# Minimum_system.net
KiCad netlist of a schematic drawn in Altium Designer
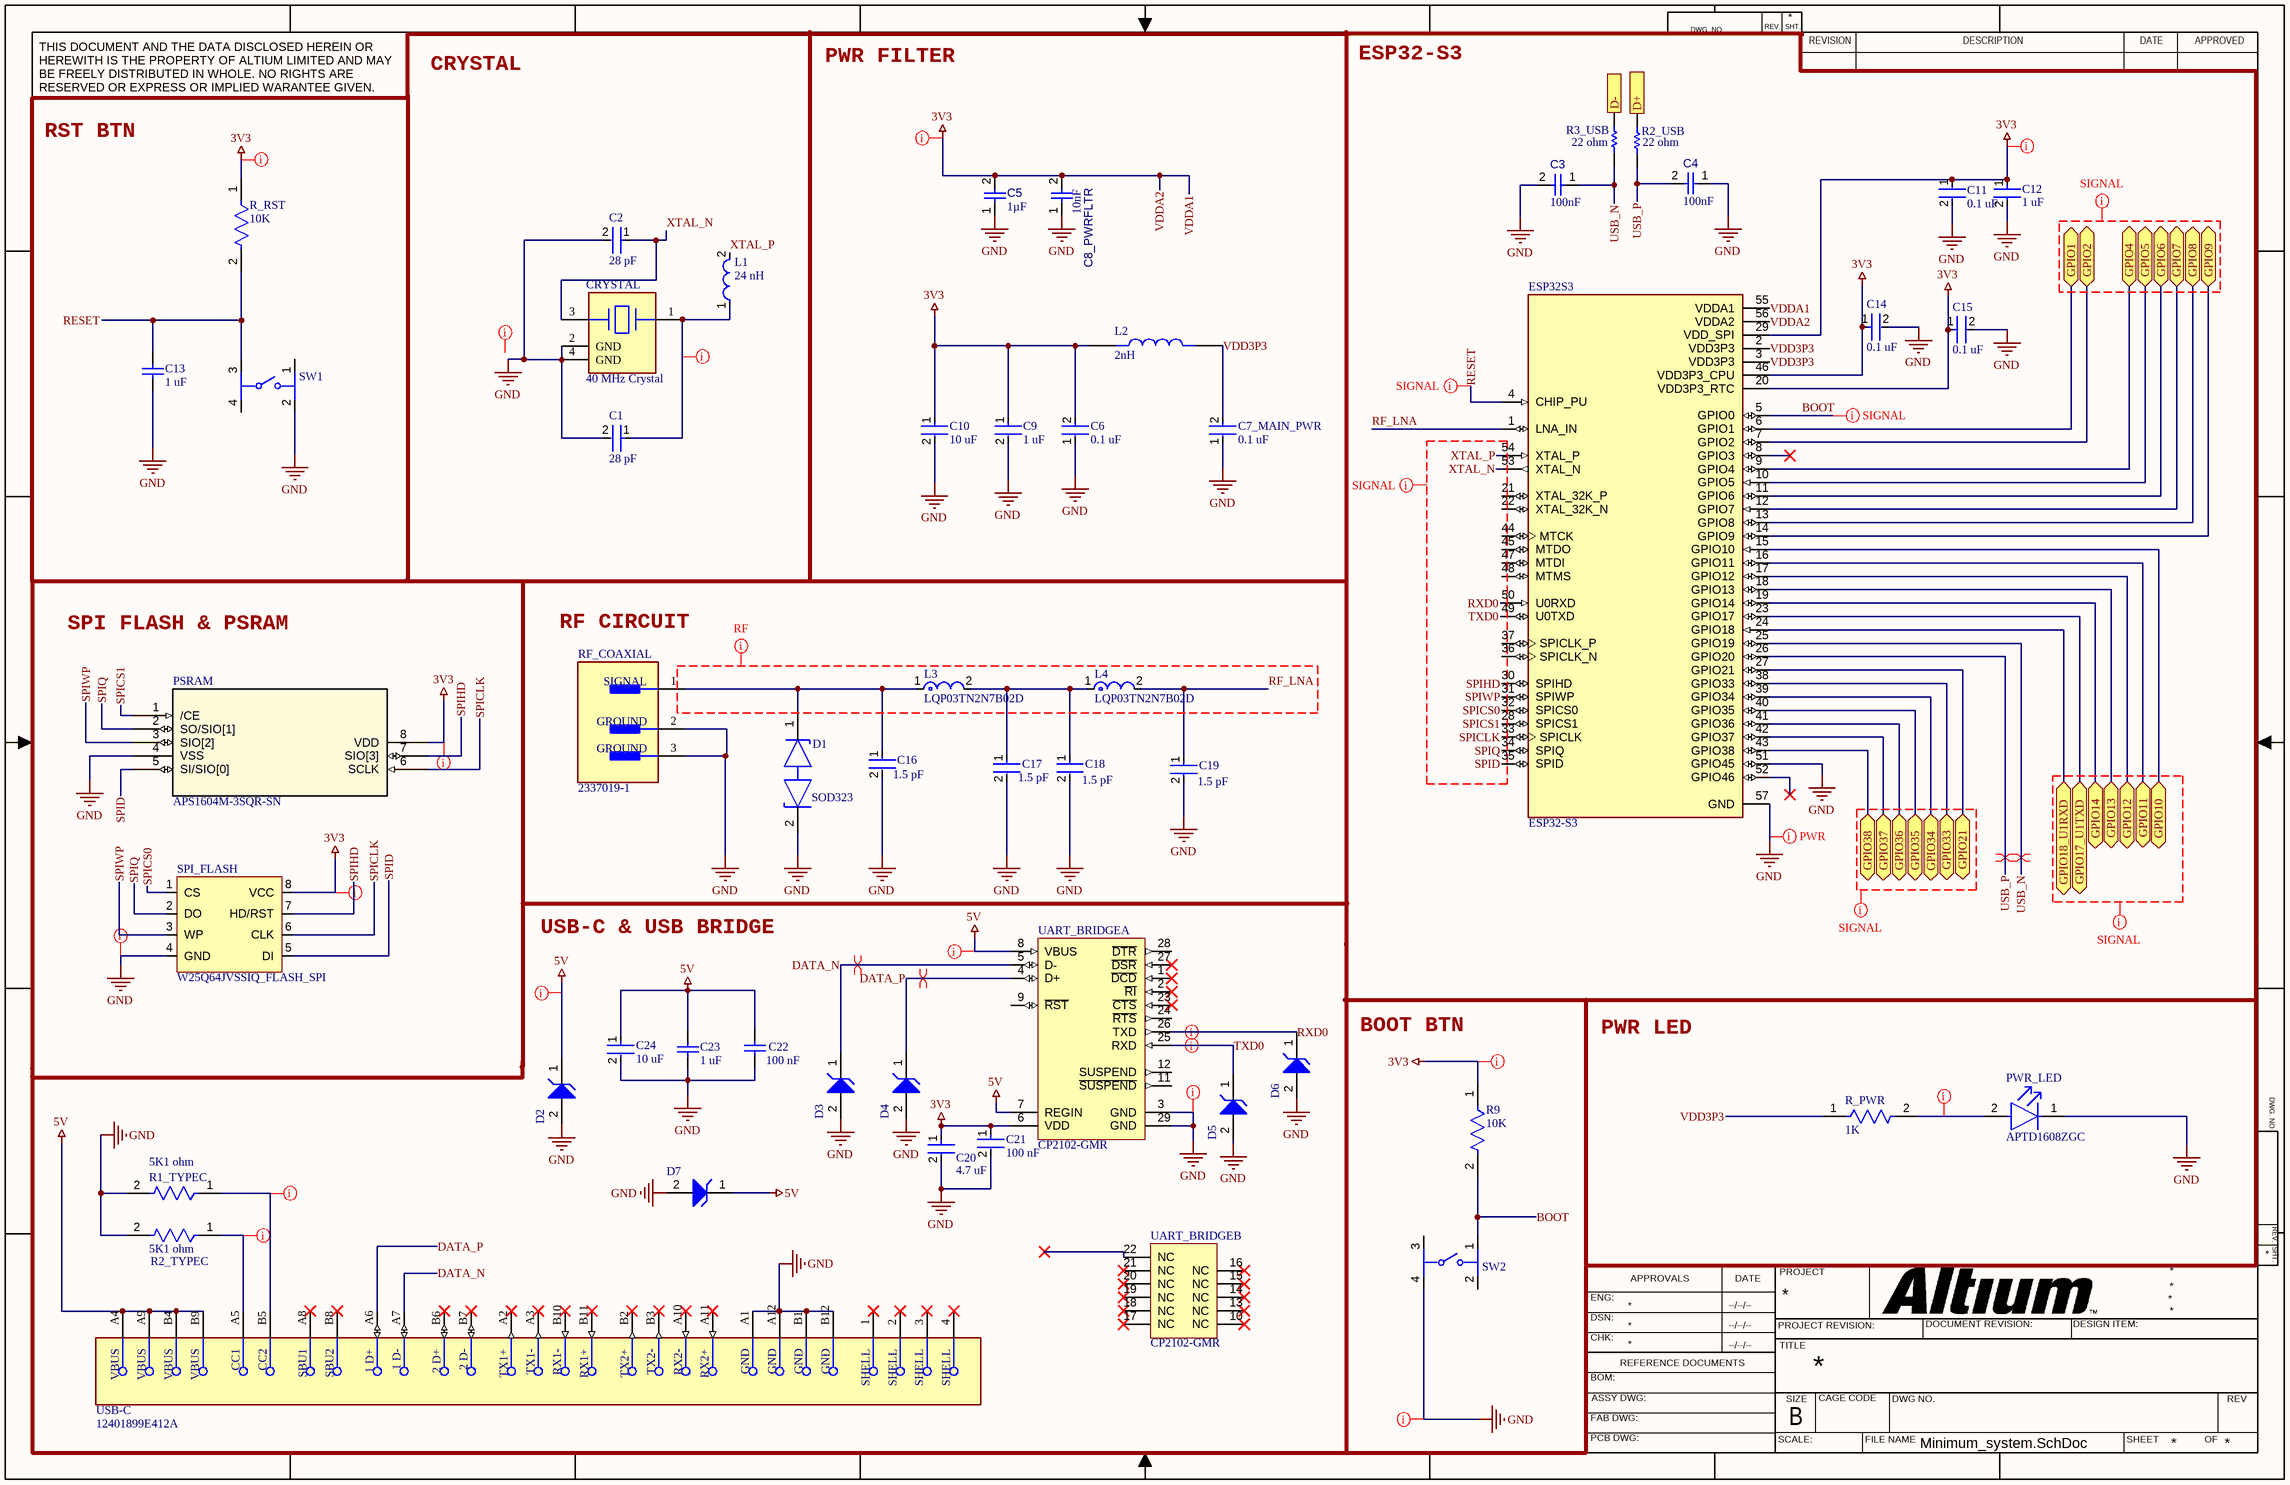
[diagram p0: Minimum_system.SchDoc]

(export (version "E")
  (design (tool "Eeschema 10.0.6"))
  (components
    (comp (ref "C1")
      (value "28 pF")
      (footprint "FP-GQM219-0_15-MFG")
      (description "Ceramic Capacitor 28pF ±2% 250VDC C0G 0805 Paper T/R")
      (libsource (lib "Altium Content Vault") (part "b4654b650e69147ec39a6b967a45e02"))
    )
    (comp (ref "C2")
      (value "28 pF")
      (footprint "FP-GQM219-0_15-MFG")
      (description "Ceramic Capacitor 28pF ±2% 250VDC C0G 0805 Paper T/R")
      (libsource (lib "Altium Content Vault") (part "b4654b650e69147ec39a6b967a45e02"))
    )
    (comp (ref "C3")
      (value "100nF")
      (footprint "CAPC0402(1005)60_L")
      (description "Chip Capacitor, 100nF +/-20%, 50V, 0402, Thickness 0.6 mm")
      (fields (field (name "TOLERANCE") "10%") (field (name "Comment") "Capacitor 100nF +/-20% 50V 0402"))
      (libsource (lib "Faiz Agunda") (part "CAP-NP-2"))
    )
    (comp (ref "C4")
      (value "100nF")
      (footprint "CAPC0402(1005)60_L")
      (description "Chip Capacitor, 100nF +/-20%, 50V, 0402, Thickness 0.6 mm")
      (fields (field (name "TOLERANCE") "10%") (field (name "Comment") "Capacitor 100nF +/-20% 50V 0402"))
      (libsource (lib "Faiz Agunda") (part "CAP-NP-2"))
    )
    (comp (ref "C5")
      (value "1µF")
      (footprint "CAPC1608X90X35ML15T15")
      (description "Chip Capacitor, 1 uF, +/- 10%, 16 V, 0603 (1608 Metric)")
      (fields (field (name "TOLERANCE") "10%") (field (name "Comment") "Capacitor 1uF +/- 10% 16V 0603"))
      (libsource (lib "Faiz Agunda") (part "CAP-NP-2"))
    )
    (comp (ref "C6")
      (value "0.1 uF")
      (footprint "FP-C1608-080-0_1-IPC_B")
      (description "Multilayer Ceramic Capacitors 100nF ±10% 50V X7R SMD 0603")
      (fields (field (name "VOLTAGE") "50V") (field (name "TOLERANCE") "10%"))
      (libsource (lib "Altium Content Vault") (part "236180d848d6139a670b325ea6854c9"))
    )
    (comp (ref "C7_MAIN_PWR")
      (value "0.1 uF")
      (footprint "FP-C1608-080-0_1-IPC_B")
      (description "Multilayer Ceramic Capacitors 100nF ±10% 50V X7R SMD 0603")
      (fields (field (name "VOLTAGE") "50V") (field (name "TOLERANCE") "10%"))
      (libsource (lib "Altium Content Vault") (part "236180d848d6139a670b325ea6854c9"))
    )
    (comp (ref "C8_PWRFLTR")
      (value "10nF")
      (footprint "CAPC0402(1005)60_L")
      (description "Chip Capacitor, 10nF +/-20%, 50V, 0402, Thickness 0.6 mm")
      (fields (field (name "TOLERANCE") "5%") (field (name "Comment") "Capacitor 10nF +/-20% 50V 0402"))
      (libsource (lib "Faiz Agunda") (part "CAP-NP-2"))
    )
    (comp (ref "C9")
      (value "1 uF")
      (footprint "FP-GRM21B-0_2-e0_2_0_7-MFG")
      (description "Chip Multilayer Ceramic Capacitors for General Purpose, 0805, 1.0uF, X7S, 22%, 10%, 100V")
      (fields (field (name "TOLERANCE") "10%"))
      (libsource (lib "Altium Content Vault") (part "b4654b650e69147ec39a6b967a45e02"))
    )
    (comp (ref "C10")
      (value "10 uF")
      (footprint "FP-GRM188-0_15-IPC_C")
      (description "Chip Multilayer Ceramic Capacitors for General Purpose, 0603, 10uF, X5R, 15%, 20%, 10V")
      (fields (field (name "TOLERANCE") "20%"))
      (libsource (lib "Altium Content Vault") (part "02cd4be3c70576c341d710602a673aa"))
    )
    (comp (ref "C11")
      (value "0.1 uF")
      (footprint "FP-C1608-080-0_1-IPC_B")
      (description "Multilayer Ceramic Capacitors 100nF ±10% 50V X7R SMD 0603")
      (fields (field (name "VOLTAGE") "50V") (field (name "TOLERANCE") "10%"))
      (libsource (lib "Altium Content Vault") (part "236180d848d6139a670b325ea6854c9"))
    )
    (comp (ref "C12")
      (value "1 uF")
      (footprint "FP-GRM21B-0_2-e0_2_0_7-MFG")
      (description "Chip Multilayer Ceramic Capacitors for General Purpose, 0805, 1.0uF, X7S, 22%, 10%, 100V")
      (fields (field (name "TOLERANCE") "10%"))
      (libsource (lib "Altium Content Vault") (part "b4654b650e69147ec39a6b967a45e02"))
    )
    (comp (ref "C13")
      (value "1 uF")
      (footprint "CAPC2013X140X50NL20T25")
      (fields
        (field (name "PART NUMBER") "0805YD105MAT2A")
        (field (name "MANUFACTURER") "AVX Interconnect / Elco")
      )
      (libsource (lib "Altium Content Vault") (part "CAP"))
    )
    (comp (ref "C14")
      (value "0.1 uF")
      (footprint "FP-CC0201-BA-MFG")
      (description "CC0201 100 nF X5R 20.00% 10 V")
      (fields (field (name "TOLERANCE") "0.2") (field (name "MANUFACTURER") "Yageo"))
      (libsource (lib "Altium Content Vault") (part "11868f565c42a9108669ba33697ecf6"))
    )
    (comp (ref "C15")
      (value "0.1 uF")
      (footprint "FP-CC0201-BA-MFG")
      (description "CC0201 100 nF X5R 20.00% 10 V")
      (fields (field (name "TOLERANCE") "0.2") (field (name "MANUFACTURER") "Yageo"))
      (libsource (lib "Altium Content Vault") (part "11868f565c42a9108669ba33697ecf6"))
    )
    (comp (ref "C16")
      (value "1.5 pF")
      (footprint "FP-GRM033-0_03-MFG")
      (description "Chip Multilayer Ceramic Capacitors for General Purpose, 0201, 1.5pF, C0G, 30ppm/°C, 0.1pF, 50V")
      (libsource (lib "Altium Content Vault") (part "b4654b650e69147ec39a6b967a45e02"))
    )
    (comp (ref "C17")
      (value "1.5 pF")
      (footprint "FP-GRM033-0_03-MFG")
      (description "Chip Multilayer Ceramic Capacitors for General Purpose, 0201, 1.5pF, C0G, 30ppm/°C, 0.1pF, 50V")
      (libsource (lib "Altium Content Vault") (part "b4654b650e69147ec39a6b967a45e02"))
    )
    (comp (ref "C18")
      (value "1.5 pF")
      (footprint "FP-GRM033-0_03-MFG")
      (description "Chip Multilayer Ceramic Capacitors for General Purpose, 0201, 1.5pF, C0G, 30ppm/°C, 0.1pF, 50V")
      (libsource (lib "Altium Content Vault") (part "b4654b650e69147ec39a6b967a45e02"))
    )
    (comp (ref "C19")
      (value "1.5 pF")
      (footprint "FP-GRM033-0_03-MFG")
      (description "Chip Multilayer Ceramic Capacitors for General Purpose, 0201, 1.5pF, C0G, 30ppm/°C, 0.1pF, 50V")
      (libsource (lib "Altium Content Vault") (part "b4654b650e69147ec39a6b967a45e02"))
    )
    (comp (ref "C20")
      (value "4.7 uF")
      (footprint "FP-GCJ31C-0_3-IPC_C")
      (description "Cap Ceramic 4.7uF 16V X7R 10% Pad SMD 1206 Soft Termination  +125°C Automotive T/R")
      (libsource (lib "Altium Content Vault") (part "b4654b650e69147ec39a6b967a45e02"))
    )
    (comp (ref "C21")
      (value "100 nF")
      (footprint "FP-GRM155-0_05-MFG")
      (description "Chip Multilayer Ceramic Capacitors for General Purpose, 0402, 0.10uF, X7R, 15%, 20%, 50V")
      (libsource (lib "Altium Content Vault") (part "02cd4be3c70576c341d710602a673aa"))
    )
    (comp (ref "C22")
      (value "100 nF")
      (footprint "CAPC0603X33X15NL03T05")
      (fields
        (field (name "PART NUMBER") "02016D104KAT4A")
        (field (name "MANUFACTURER") "AVX Interconnect / Elco")
      )
      (libsource (lib "Altium Content Vault") (part "CAP"))
    )
    (comp (ref "C23")
      (value "1 uF")
      (footprint "CAPC2013X140X50NL20T25")
      (fields
        (field (name "PART NUMBER") "0805YD105MAT2A")
        (field (name "MANUFACTURER") "AVX Interconnect / Elco")
      )
      (libsource (lib "Altium Content Vault") (part "CAP"))
    )
    (comp (ref "C24")
      (value "10 uF")
      (footprint "FP-GRM188-0_15-IPC_C")
      (description "Chip Multilayer Ceramic Capacitors for General Purpose, 0603, 10uF, X5R, 15%, 20%, 10V")
      (fields (field (name "TOLERANCE") "20%"))
      (libsource (lib "Altium Content Vault") (part "02cd4be3c70576c341d710602a673aa"))
    )
    (comp (ref "CRYSTAL")
      (value "40 MHz Crystal")
      (footprint "FP-ABM8AIG-MFG")
      (description "Crystal 40MHz ±20ppm (Tol) ±100ppm (Stability) 12pF FUND 35Ω Automotive 4-Pin Ultra Mini-CSMD T/R")
      (libsource (lib "Altium Content Vault") (part "5645ab55de99a04feaa93ac4102b7fe"))
    )
    (comp (ref "D1")
      (value "SOD323")
      (footprint "FP-SOD323-CA-MFG")
      (description "TVS DIODE 5V 14V SOD323")
      (libsource (lib "Altium Content Vault") (part "f6dbb2535d6b2d347ec798cb4d032a4"))
    )
    (comp (ref "D2")
      (value "824520581")
      (footprint "WE-TVSP_DO-214AA_Unidirectional")
      (description "TVS diode [Würth Elektronik] 824520581 TVS diode")
      (libsource (lib "Altium Content Vault") (part "WE-TVSP_Unidirectional"))
    )
    (comp (ref "D3")
      (value "824520581")
      (footprint "WE-TVSP_DO-214AA_Unidirectional")
      (description "TVS diode [Würth Elektronik] 824520581 TVS diode")
      (libsource (lib "Altium Content Vault") (part "WE-TVSP_Unidirectional"))
    )
    (comp (ref "D4")
      (value "824520581")
      (footprint "WE-TVSP_DO-214AA_Unidirectional")
      (description "TVS diode [Würth Elektronik] 824520581 TVS diode")
      (libsource (lib "Altium Content Vault") (part "WE-TVSP_Unidirectional"))
    )
    (comp (ref "D5")
      (value "824520581")
      (footprint "WE-TVSP_DO-214AA_Unidirectional")
      (description "TVS diode [Würth Elektronik] 824520581 TVS diode")
      (libsource (lib "Altium Content Vault") (part "WE-TVSP_Unidirectional"))
    )
    (comp (ref "D6")
      (value "824520581")
      (footprint "WE-TVSP_DO-214AA_Unidirectional")
      (description "TVS diode [Würth Elektronik] 824520581 TVS diode")
      (libsource (lib "Altium Content Vault") (part "WE-TVSP_Unidirectional"))
    )
    (comp (ref "D7")
      (value "824520581")
      (footprint "WE-TVSP_DO-214AA_Unidirectional")
      (description "TVS diode [Würth Elektronik] 824520581 TVS diode")
      (libsource (lib "Altium Content Vault") (part "WE-TVSP_Unidirectional"))
    )
    (comp (ref "ESP32S3")
      (value "ESP32-S3")
      (footprint "IC_ESP32-S3")
      (fields (field (name "MF") "Espressif Systems"))
      (libsource (lib "Faiz Agunda") (part "ESP32-S3"))
    )
    (comp (ref "L1")
      (value "24 nH")
      (footprint "FP-LQW15AN_00-W0_5-0_1-MFG")
      (description "Wire Wound RF Inductor 24nH ±2% 280mA 0.52Ω 0402 (1005)")
      (fields (field (name "TOLERANCE") "2%"))
      (libsource (lib "Altium Content Vault") (part "725321dda6339637d4d059423bc1c3c"))
    )
    (comp (ref "L2")
      (value "2nH")
      (footprint "INDC0603X28N")
      (fields (field (name "MP") "ATFC-0201HQ-2N0B-T") (field (name "MF") "{'manufacturer': u'Abracon LLC'}"))
      (libsource (lib "Faiz Agunda") (part "ATFC-0201HQ-2N0B-T"))
    )
    (comp (ref "L3")
      (value "LQP03TN2N7B02D")
      (footprint "FP-LQP03TG_02-IPC_A")
      (description "Film type RF Inductor 2.7nH ±0.1nH 500mA 0.2Ω 0201 (0603)")
      (fields (field (name "TOLERANCE") "3%"))
      (libsource (lib "Altium Content Vault") (part "4cc4b267dca4c8e51f7102f422741d8"))
    )
    (comp (ref "L4")
      (value "LQP03TN2N7B02D")
      (footprint "FP-LQP03TG_02-IPC_A")
      (description "Film type RF Inductor 2.7nH ±0.1nH 500mA 0.2Ω 0201 (0603)")
      (fields (field (name "TOLERANCE") "3%"))
      (libsource (lib "Altium Content Vault") (part "4cc4b267dca4c8e51f7102f422741d8"))
    )
    (comp (ref "PSRAM")
      (value "APS1604M-3SQR-SN")
      (footprint "SOP8L_APS1604M-3SQR-SN_APY")
      (description "2 MB PSRAM SPI")
      (fields (field (name "COPYRIGHT") "Copyright (C) 2026 Ultra Librarian. All rights reserved."))
      (libsource (lib "Faiz Agunda") (part "APS1604M-3SQR-SN"))
    )
    (comp (ref "PWR_LED")
      (value "APTD1608ZGC")
      (footprint "FP-APTD1608ZGC-MFG")
      (description "LED GREEN CLEAR CHIP SMD")
      (libsource (lib "Altium Content Vault") (part "8706943c75ba83719d021d2fdc84c58"))
    )
    (comp (ref "R1_TYPEC")
      (value "5K1 ohm")
      (footprint "FP-CRCW1206-e3-IPC_B")
      (description "RES Thick Film, 5.1kΩ, 5%, 0.25W, 200ppm/°C, 1206")
      (fields (field (name "TOLERANCE") "5%"))
      (libsource (lib "Altium Content Vault") (part "1029c3af85768c4190bb7ad29bc67b5"))
    )
    (comp (ref "R2_TYPEC")
      (value "5K1 ohm")
      (footprint "FP-CRCW1206-e3-IPC_B")
      (description "RES Thick Film, 5.1kΩ, 5%, 0.25W, 200ppm/°C, 1206")
      (fields (field (name "TOLERANCE") "5%"))
      (libsource (lib "Altium Content Vault") (part "1029c3af85768c4190bb7ad29bc67b5"))
    )
    (comp (ref "R2_USB")
      (value "22 ohm")
      (footprint "RESC1608X55X25LL10T15")
      (fields (field (name "MANUFACTURER") "Yageo") (field (name "PART NUMBER") "RC0603FR-1022RL"))
      (libsource (lib "Altium Content Vault") (part "RES"))
    )
    (comp (ref "R3_USB")
      (value "22 ohm")
      (footprint "RESC1608X55X25LL10T15")
      (fields (field (name "MANUFACTURER") "Yageo") (field (name "PART NUMBER") "RC0603FR-1022RL"))
      (libsource (lib "Altium Content Vault") (part "RES"))
    )
    (comp (ref "R9")
      (value "10K")
      (footprint "FP-AC0603-IPC_A")
      (description "RES 10kΩ 5.00% 0.2W 0603")
      (libsource (lib "Altium Content Vault") (part "1029c3af85768c4190bb7ad29bc67b5"))
    )
    (comp (ref "RF_COAXIAL")
      (value "2337019-1")
      (footprint "FP-2337019-1-MFG")
      (description "UMCC MICRO-COAX RECEPTACLE, GEN")
      (libsource (lib "Altium Content Vault") (part "3efd87c86022015edd7e825a7948772"))
    )
    (comp (ref "R_PWR")
      (value "1K")
      (footprint "FP-RP732B-MFG")
      (description "Res Thin Film 1206 1.0KΩ 0.1% 0.25W 15ppm/°C Molded SMD")
      (fields
        (field (name "TOLERANCE") "0.1%")
        (field (name "OCTOPART") "https://octopart.com/rp73d2b1k0btdf-te+connectivity-22741139")
      )
      (libsource (lib "Altium Content Vault") (part "1029c3af85768c4190bb7ad29bc67b5"))
    )
    (comp (ref "R_RST")
      (value "10K")
      (footprint "FP-AC0603-IPC_A")
      (description "RES 10kΩ 5.00% 0.2W 0603")
      (libsource (lib "Altium Content Vault") (part "1029c3af85768c4190bb7ad29bc67b5"))
    )
    (comp (ref "SPI_FLASH")
      (value "W25Q64JVSSIQ_FLASH_SPI")
      (footprint "SOIC127P790X216-8N")
      (description "8 MB flash SPI")
      (libsource (lib "Faiz Agunda") (part "Component_1"))
    )
    (comp (ref "SW1")
      (value "PTS810SJM250SMTRLFS")
      (footprint "FP-PTS810SJM250SMTRLFS-MFG")
      (description "SWITCH TACTILE SPST-NO 0.05A 16V")
      (libsource (lib "Altium Content Vault") (part "1adf0dd01260c80cf25a44bfd6b99ba"))
    )
    (comp (ref "SW2")
      (value "PTS810SJM250SMTRLFS")
      (footprint "FP-PTS810SJM250SMTRLFS-MFG")
      (description "SWITCH TACTILE SPST-NO 0.05A 16V")
      (libsource (lib "Altium Content Vault") (part "1adf0dd01260c80cf25a44bfd6b99ba"))
    )
    (comp (ref "UART_BRIDGE")
      (value "CP2102-GMR")
      (footprint "SLAB-QFN-28-3125x3125TP_M")
      (description "Single-Chip USB to URAT Bridge, 3.3 V, -40 to 85 degC, 28-Pin QFN, RoHS, Tape and Reel")
      (fields (field (name "MANUFACTURER") "Silicon Labs"))
      (libsource (lib "Altium Content Vault") (part "SLAB-CP210X-QFN-28-29"))
    )
    (comp (ref "USB-C")
      (value "12401899E412A")
      (footprint "FP-12401899E412A-MFG")
      (description "USB TYPE C, RECEPTACLE, TOP MOUN")
      (libsource (lib "Altium Content Vault") (part "d6c81757777e40fb740c912bc321649"))
    )
  )
  (nets
    (net (code "2") (name "/BOOT") (class "Default")
      (node (ref "ESP32S3") (pin "5") (pinfunction "GPIO0_5") (pintype "bidirectional"))
      (node (ref "R9") (pin "2") (pinfunction "2_2") (pintype "passive"))
      (node (ref "SW2") (pin "1") (pinfunction "1_1") (pintype "passive"))
    )
    (net (code "3") (name "/D+") (class "Default")
      (node (ref "R2_USB") (pin "1") (pinfunction "1_1") (pintype "passive"))
    )
    (net (code "4") (name "/D-") (class "Default")
      (node (ref "R3_USB") (pin "1") (pinfunction "1_1") (pintype "passive"))
    )
    (net (code "5") (name "/DATA_N") (class "Default")
      (node (ref "D3") (pin "1") (pinfunction "K_1") (pintype "passive"))
      (node (ref "UART_BRIDGE") (pin "5") (pinfunction "D-_5") (pintype "bidirectional"))
      (node (ref "USB-C") (pin "A7") (pinfunction "1_D-_A7") (pintype "bidirectional"))
    )
    (net (code "6") (name "/DATA_P") (class "Default")
      (node (ref "D4") (pin "1") (pinfunction "K_1") (pintype "passive"))
      (node (ref "UART_BRIDGE") (pin "4") (pinfunction "D+_4") (pintype "bidirectional"))
      (node (ref "USB-C") (pin "A6") (pinfunction "1_D+_A6") (pintype "bidirectional"))
    )
    (net (code "7") (name "/GPIO1") (class "Default")
      (node (ref "ESP32S3") (pin "6") (pinfunction "GPIO1_6") (pintype "bidirectional"))
    )
    (net (code "8") (name "/GPIO2") (class "Default")
      (node (ref "ESP32S3") (pin "7") (pinfunction "GPIO2_7") (pintype "bidirectional"))
    )
    (net (code "9") (name "/GPIO4") (class "Default")
      (node (ref "ESP32S3") (pin "9") (pinfunction "GPIO4_9") (pintype "bidirectional"))
    )
    (net (code "10") (name "/GPIO5") (class "Default")
      (node (ref "ESP32S3") (pin "10") (pinfunction "GPIO5_10") (pintype "input"))
    )
    (net (code "11") (name "/GPIO6") (class "Default")
      (node (ref "ESP32S3") (pin "11") (pinfunction "GPIO6_11") (pintype "bidirectional"))
    )
    (net (code "12") (name "/GPIO7") (class "Default")
      (node (ref "ESP32S3") (pin "12") (pinfunction "GPIO7_12") (pintype "input"))
    )
    (net (code "13") (name "/GPIO8") (class "Default")
      (node (ref "ESP32S3") (pin "13") (pinfunction "GPIO8_13") (pintype "bidirectional"))
    )
    (net (code "14") (name "/GPIO9") (class "Default")
      (node (ref "ESP32S3") (pin "14") (pinfunction "GPIO9_14") (pintype "bidirectional"))
    )
    (net (code "15") (name "/GPIO10") (class "Default")
      (node (ref "ESP32S3") (pin "15") (pinfunction "GPIO10_15") (pintype "input"))
    )
    (net (code "16") (name "/GPIO11") (class "Default")
      (node (ref "ESP32S3") (pin "16") (pinfunction "GPIO11_16") (pintype "bidirectional"))
    )
    (net (code "17") (name "/GPIO12") (class "Default")
      (node (ref "ESP32S3") (pin "17") (pinfunction "GPIO12_17") (pintype "bidirectional"))
    )
    (net (code "18") (name "/GPIO13") (class "Default")
      (node (ref "ESP32S3") (pin "18") (pinfunction "GPIO13_18") (pintype "bidirectional"))
    )
    (net (code "19") (name "/GPIO14") (class "Default")
      (node (ref "ESP32S3") (pin "19") (pinfunction "GPIO14_19") (pintype "bidirectional"))
    )
    (net (code "20") (name "/GPIO17_U1TXD") (class "Default")
      (node (ref "ESP32S3") (pin "23") (pinfunction "GPIO17_23") (pintype "bidirectional"))
    )
    (net (code "21") (name "/GPIO18_U1RXD") (class "Default")
      (node (ref "ESP32S3") (pin "24") (pinfunction "GPIO18_24") (pintype "input"))
    )
    (net (code "22") (name "/GPIO21") (class "Default")
      (node (ref "ESP32S3") (pin "27") (pinfunction "GPIO21_27") (pintype "bidirectional"))
    )
    (net (code "23") (name "/GPIO33") (class "Default")
      (node (ref "ESP32S3") (pin "38") (pinfunction "GPIO33_38") (pintype "bidirectional"))
    )
    (net (code "24") (name "/GPIO34") (class "Default")
      (node (ref "ESP32S3") (pin "39") (pinfunction "GPIO34_39") (pintype "bidirectional"))
    )
    (net (code "25") (name "/GPIO35") (class "Default")
      (node (ref "ESP32S3") (pin "40") (pinfunction "GPIO35_40") (pintype "bidirectional"))
    )
    (net (code "26") (name "/GPIO36") (class "Default")
      (node (ref "ESP32S3") (pin "41") (pinfunction "GPIO36_41") (pintype "bidirectional"))
    )
    (net (code "27") (name "/GPIO37") (class "Default")
      (node (ref "ESP32S3") (pin "42") (pinfunction "GPIO37_42") (pintype "bidirectional"))
    )
    (net (code "28") (name "/GPIO38") (class "Default")
      (node (ref "ESP32S3") (pin "43") (pinfunction "GPIO38_43") (pintype "bidirectional"))
    )
    (net (code "29") (name "/RESET") (class "Default")
      (node (ref "C13") (pin "1") (pinfunction "1_1") (pintype "passive"))
      (node (ref "ESP32S3") (pin "4") (pinfunction "CHIP_PU_4") (pintype "input"))
      (node (ref "R_RST") (pin "2") (pinfunction "2_2") (pintype "passive"))
      (node (ref "SW1") (pin "3") (pinfunction "3_3") (pintype "passive"))
    )
    (net (code "30") (name "/RF_LNA") (class "Default")
      (node (ref "C19") (pin "1") (pinfunction "1_1") (pintype "passive"))
      (node (ref "ESP32S3") (pin "1") (pinfunction "LNA_IN_1") (pintype "bidirectional"))
      (node (ref "L4") (pin "2") (pinfunction "2_2") (pintype "passive"))
    )
    (net (code "31") (name "/RXD0") (class "Default")
      (node (ref "D6") (pin "1") (pinfunction "K_1") (pintype "passive"))
      (node (ref "ESP32S3") (pin "50") (pinfunction "U0RXD_50") (pintype "input"))
      (node (ref "UART_BRIDGE") (pin "26") (pinfunction "TXD_26") (pintype "output"))
    )
    (net (code "32") (name "/SPICLK") (class "Default")
      (node (ref "ESP32S3") (pin "33") (pinfunction "SPICLK_33") (pintype "bidirectional"))
      (node (ref "PSRAM") (pin "6") (pinfunction "SCLK_6") (pintype "input"))
      (node (ref "SPI_FLASH") (pin "6") (pinfunction "CLK_6") (pintype "passive"))
    )
    (net (code "33") (name "/SPICS0") (class "Default")
      (node (ref "ESP32S3") (pin "32") (pinfunction "SPICS0_32") (pintype "bidirectional"))
      (node (ref "SPI_FLASH") (pin "1") (pinfunction "CS_1") (pintype "passive"))
    )
    (net (code "34") (name "/SPICS1") (class "Default")
      (node (ref "ESP32S3") (pin "28") (pinfunction "SPICS1_28") (pintype "bidirectional"))
      (node (ref "PSRAM") (pin "1") (pinfunction "/CE_1") (pintype "input"))
    )
    (net (code "35") (name "/SPID") (class "Default")
      (node (ref "ESP32S3") (pin "35") (pinfunction "SPID_35") (pintype "bidirectional"))
      (node (ref "PSRAM") (pin "5") (pinfunction "SI/SIO[0]_5") (pintype "bidirectional"))
      (node (ref "SPI_FLASH") (pin "5") (pinfunction "DI_5") (pintype "passive"))
    )
    (net (code "36") (name "/SPIHD") (class "Default")
      (node (ref "ESP32S3") (pin "30") (pinfunction "SPIHD_30") (pintype "bidirectional"))
      (node (ref "PSRAM") (pin "7") (pinfunction "SIO[3]_7") (pintype "bidirectional"))
      (node (ref "SPI_FLASH") (pin "7") (pinfunction "HD/RST_7") (pintype "passive"))
    )
    (net (code "37") (name "/SPIQ") (class "Default")
      (node (ref "ESP32S3") (pin "34") (pinfunction "SPIQ_34") (pintype "bidirectional"))
      (node (ref "PSRAM") (pin "2") (pinfunction "SO/SIO[1]_2") (pintype "bidirectional"))
      (node (ref "SPI_FLASH") (pin "2") (pinfunction "DO_2") (pintype "passive"))
    )
    (net (code "38") (name "/SPIWP") (class "Default")
      (node (ref "ESP32S3") (pin "31") (pinfunction "SPIWP_31") (pintype "bidirectional"))
      (node (ref "PSRAM") (pin "3") (pinfunction "SIO[2]_3") (pintype "bidirectional"))
      (node (ref "SPI_FLASH") (pin "3") (pinfunction "WP_3") (pintype "passive"))
    )
    (net (code "39") (name "/TXD0") (class "Default")
      (node (ref "D5") (pin "1") (pinfunction "K_1") (pintype "passive"))
      (node (ref "ESP32S3") (pin "49") (pinfunction "U0TXD_49") (pintype "bidirectional"))
      (node (ref "UART_BRIDGE") (pin "25") (pinfunction "RXD_25") (pintype "input"))
    )
    (net (code "40") (name "/USB_N") (class "Default")
      (node (ref "C3") (pin "1") (pinfunction "1_1") (pintype "passive"))
      (node (ref "ESP32S3") (pin "25") (pinfunction "GPIO19_25") (pintype "bidirectional"))
      (node (ref "R3_USB") (pin "2") (pinfunction "2_2") (pintype "passive"))
    )
    (net (code "41") (name "/USB_P") (class "Default")
      (node (ref "C4") (pin "2") (pinfunction "2_2") (pintype "passive"))
      (node (ref "ESP32S3") (pin "26") (pinfunction "GPIO20_26") (pintype "bidirectional"))
      (node (ref "R2_USB") (pin "2") (pinfunction "2_2") (pintype "passive"))
    )
    (net (code "42") (name "/VDD3P3") (class "Default")
      (node (ref "C7_MAIN_PWR") (pin "2") (pinfunction "2_2") (pintype "passive"))
      (node (ref "ESP32S3") (pin "2") (pinfunction "VDD3P3_2") (pintype "power_in"))
      (node (ref "ESP32S3") (pin "3") (pinfunction "VDD3P3_3") (pintype "power_in"))
      (node (ref "L2") (pin "2") (pinfunction "2_2") (pintype "passive"))
      (node (ref "R_PWR") (pin "1") (pinfunction "1_1") (pintype "passive"))
    )
    (net (code "43") (name "/XTAL_N") (class "Default")
      (node (ref "C2") (pin "1") (pinfunction "1_1") (pintype "passive"))
      (node (ref "CRYSTAL") (pin "3") (pinfunction "3_3") (pintype "passive"))
      (node (ref "ESP32S3") (pin "53") (pinfunction "XTAL_N_53") (pintype "output"))
    )
    (net (code "44") (name "/XTAL_P") (class "Default")
      (node (ref "ESP32S3") (pin "54") (pinfunction "XTAL_P_54") (pintype "input"))
      (node (ref "L1") (pin "2") (pinfunction "2_2") (pintype "passive"))
    )
    (net (code "45") (name "3V3") (class "Default")
      (node (ref "C10") (pin "1") (pinfunction "1_1") (pintype "passive"))
      (node (ref "C11") (pin "1") (pinfunction "1_1") (pintype "passive"))
      (node (ref "C12") (pin "1") (pinfunction "1_1") (pintype "passive"))
      (node (ref "C14") (pin "1") (pinfunction "1_1") (pintype "passive"))
      (node (ref "C15") (pin "1") (pinfunction "1_1") (pintype "passive"))
      (node (ref "C20") (pin "1") (pinfunction "1_1") (pintype "passive"))
      (node (ref "C21") (pin "1") (pinfunction "1_1") (pintype "passive"))
      (node (ref "C5") (pin "2") (pinfunction "2_2") (pintype "passive"))
      (node (ref "C6") (pin "2") (pinfunction "2_2") (pintype "passive"))
      (node (ref "C8_PWRFLTR") (pin "2") (pinfunction "2_2") (pintype "passive"))
      (node (ref "C9") (pin "1") (pinfunction "1_1") (pintype "passive"))
      (node (ref "ESP32S3") (pin "20") (pinfunction "VDD3P3_RTC_20") (pintype "power_in"))
      (node (ref "ESP32S3") (pin "29") (pinfunction "VDD_SPI_29") (pintype "power_in"))
      (node (ref "ESP32S3") (pin "46") (pinfunction "VDD3P3_CPU_46") (pintype "power_in"))
      (node (ref "ESP32S3") (pin "55") (pinfunction "VDDA1_55") (pintype "power_in"))
      (node (ref "ESP32S3") (pin "56") (pinfunction "VDDA2_56") (pintype "power_in"))
      (node (ref "L2") (pin "1") (pinfunction "1_1") (pintype "passive"))
      (node (ref "PSRAM") (pin "8") (pinfunction "VDD_8") (pintype "power_in"))
      (node (ref "R9") (pin "1") (pinfunction "1_1") (pintype "passive"))
      (node (ref "R_RST") (pin "1") (pinfunction "1_1") (pintype "passive"))
      (node (ref "SPI_FLASH") (pin "8") (pinfunction "VCC_8") (pintype "passive"))
      (node (ref "UART_BRIDGE") (pin "6") (pinfunction "VDD_6") (pintype "power_in"))
    )
    (net (code "46") (name "5V") (class "Default")
      (node (ref "C22") (pin "2") (pinfunction "2_2") (pintype "passive"))
      (node (ref "C23") (pin "1") (pinfunction "1_1") (pintype "passive"))
      (node (ref "C24") (pin "1") (pinfunction "1_1") (pintype "passive"))
      (node (ref "D2") (pin "1") (pinfunction "K_1") (pintype "passive"))
      (node (ref "D7") (pin "1") (pinfunction "K_1") (pintype "passive"))
      (node (ref "UART_BRIDGE") (pin "7") (pinfunction "REGIN_7") (pintype "power_in"))
      (node (ref "UART_BRIDGE") (pin "8") (pinfunction "VBUS_8") (pintype "input"))
      (node (ref "USB-C") (pin "A4") (pinfunction "VBUS_A4") (pintype "power_in"))
      (node (ref "USB-C") (pin "A9") (pinfunction "VBUS_A9") (pintype "power_in"))
      (node (ref "USB-C") (pin "B4") (pinfunction "VBUS_B4") (pintype "power_in"))
      (node (ref "USB-C") (pin "B9") (pinfunction "VBUS_B9") (pintype "power_in"))
    )
    (net (code "47") (name "GND") (class "Default")
      (node (ref "C1") (pin "2") (pinfunction "2_2") (pintype "passive"))
      (node (ref "C10") (pin "2") (pinfunction "2_2") (pintype "passive"))
      (node (ref "C11") (pin "2") (pinfunction "2_2") (pintype "passive"))
      (node (ref "C12") (pin "2") (pinfunction "2_2") (pintype "passive"))
      (node (ref "C13") (pin "2") (pinfunction "2_2") (pintype "passive"))
      (node (ref "C14") (pin "2") (pinfunction "2_2") (pintype "passive"))
      (node (ref "C15") (pin "2") (pinfunction "2_2") (pintype "passive"))
      (node (ref "C16") (pin "2") (pinfunction "2_2") (pintype "passive"))
      (node (ref "C17") (pin "2") (pinfunction "2_2") (pintype "passive"))
      (node (ref "C18") (pin "2") (pinfunction "2_2") (pintype "passive"))
      (node (ref "C19") (pin "2") (pinfunction "2_2") (pintype "passive"))
      (node (ref "C2") (pin "2") (pinfunction "2_2") (pintype "passive"))
      (node (ref "C20") (pin "2") (pinfunction "2_2") (pintype "passive"))
      (node (ref "C21") (pin "2") (pinfunction "2_2") (pintype "passive"))
      (node (ref "C22") (pin "1") (pinfunction "1_1") (pintype "passive"))
      (node (ref "C23") (pin "2") (pinfunction "2_2") (pintype "passive"))
      (node (ref "C24") (pin "2") (pinfunction "2_2") (pintype "passive"))
      (node (ref "C3") (pin "2") (pinfunction "2_2") (pintype "passive"))
      (node (ref "C4") (pin "1") (pinfunction "1_1") (pintype "passive"))
      (node (ref "C5") (pin "1") (pinfunction "1_1") (pintype "passive"))
      (node (ref "C6") (pin "1") (pinfunction "1_1") (pintype "passive"))
      (node (ref "C7_MAIN_PWR") (pin "1") (pinfunction "1_1") (pintype "passive"))
      (node (ref "C8_PWRFLTR") (pin "1") (pinfunction "1_1") (pintype "passive"))
      (node (ref "C9") (pin "2") (pinfunction "2_2") (pintype "passive"))
      (node (ref "CRYSTAL") (pin "2") (pinfunction "GND_2") (pintype "power_in"))
      (node (ref "CRYSTAL") (pin "4") (pinfunction "GND_4") (pintype "power_in"))
      (node (ref "D1") (pin "2") (pinfunction "K2_2") (pintype "passive"))
      (node (ref "D2") (pin "2") (pinfunction "A_2") (pintype "passive"))
      (node (ref "D3") (pin "2") (pinfunction "A_2") (pintype "passive"))
      (node (ref "D4") (pin "2") (pinfunction "A_2") (pintype "passive"))
      (node (ref "D5") (pin "2") (pinfunction "A_2") (pintype "passive"))
      (node (ref "D6") (pin "2") (pinfunction "A_2") (pintype "passive"))
      (node (ref "D7") (pin "2") (pinfunction "A_2") (pintype "passive"))
      (node (ref "ESP32S3") (pin "51") (pinfunction "GPIO45_51") (pintype "bidirectional"))
      (node (ref "ESP32S3") (pin "57") (pinfunction "GND_57") (pintype "power_in"))
      (node (ref "PSRAM") (pin "4") (pinfunction "VSS_4") (pintype "power_in"))
      (node (ref "PWR_LED") (pin "1") (pinfunction "C_1") (pintype "passive"))
      (node (ref "R1_TYPEC") (pin "2") (pinfunction "2_2") (pintype "passive"))
      (node (ref "R2_TYPEC") (pin "2") (pinfunction "2_2") (pintype "passive"))
      (node (ref "RF_COAXIAL") (pin "2") (pinfunction "GROUND_2") (pintype "power_in"))
      (node (ref "RF_COAXIAL") (pin "3") (pinfunction "GROUND_3") (pintype "power_in"))
      (node (ref "SPI_FLASH") (pin "4") (pinfunction "GND_4") (pintype "passive"))
      (node (ref "SW1") (pin "2") (pinfunction "2_2") (pintype "passive"))
      (node (ref "SW2") (pin "4") (pinfunction "4_4") (pintype "passive"))
      (node (ref "UART_BRIDGE") (pin "29") (pinfunction "GND_29") (pintype "power_in"))
      (node (ref "UART_BRIDGE") (pin "3") (pinfunction "GND_3") (pintype "power_in"))
      (node (ref "USB-C") (pin "A1") (pinfunction "GND_A1") (pintype "power_in"))
      (node (ref "USB-C") (pin "A12") (pinfunction "GND_A12") (pintype "power_in"))
      (node (ref "USB-C") (pin "B1") (pinfunction "GND_B1") (pintype "power_in"))
      (node (ref "USB-C") (pin "B12") (pinfunction "GND_B12") (pintype "power_in"))
    )
    (net (code "48") (name "Net-(C1-Pad1)") (class "Default")
      (node (ref "C1") (pin "1") (pinfunction "1_1") (pintype "passive"))
      (node (ref "CRYSTAL") (pin "1") (pinfunction "1_1") (pintype "passive"))
      (node (ref "L1") (pin "1") (pinfunction "1_1") (pintype "passive"))
    )
    (net (code "49") (name "Net-(C17-Pad1)") (class "Default")
      (node (ref "C17") (pin "1") (pinfunction "1_1") (pintype "passive"))
      (node (ref "C18") (pin "1") (pinfunction "1_1") (pintype "passive"))
      (node (ref "L3") (pin "2") (pinfunction "2_2") (pintype "passive"))
      (node (ref "L4") (pin "1") (pinfunction "1_1") (pintype "passive"))
    )
    (net (code "50") (name "Net-(D1-K1)") (class "Default")
      (node (ref "C16") (pin "1") (pinfunction "1_1") (pintype "passive"))
      (node (ref "D1") (pin "1") (pinfunction "K1_1") (pintype "passive"))
      (node (ref "L3") (pin "1") (pinfunction "1_1") (pintype "passive"))
      (node (ref "RF_COAXIAL") (pin "1") (pinfunction "SIGNAL_1") (pintype "passive"))
    )
    (net (code "51") (name "Net-(PWR_LED-A)") (class "Default")
      (node (ref "PWR_LED") (pin "2") (pinfunction "A_2") (pintype "passive"))
      (node (ref "R_PWR") (pin "2") (pinfunction "2_2") (pintype "passive"))
    )
    (net (code "52") (name "Net-(USB-C-CC1)") (class "Default")
      (node (ref "R2_TYPEC") (pin "1") (pinfunction "1_1") (pintype "passive"))
      (node (ref "USB-C") (pin "A5") (pinfunction "CC1_A5") (pintype "passive"))
    )
    (net (code "53") (name "Net-(USB-C-CC2)") (class "Default")
      (node (ref "R1_TYPEC") (pin "1") (pinfunction "1_1") (pintype "passive"))
      (node (ref "USB-C") (pin "B5") (pinfunction "CC2_B5") (pintype "passive"))
    )
    (net (code "54") (name "unconnected-(ESP32S3-GPIO3-Pad8)") (class "Default")
      (node (ref "ESP32S3") (pin "8") (pinfunction "GPIO3_8") (pintype "bidirectional+no_connect"))
    )
    (net (code "55") (name "unconnected-(ESP32S3-GPIO46-Pad52)") (class "Default")
      (node (ref "ESP32S3") (pin "52") (pinfunction "GPIO46_52") (pintype "bidirectional+no_connect"))
    )
    (net (code "56") (name "unconnected-(ESP32S3-MTCK-Pad44)") (class "Default")
      (node (ref "ESP32S3") (pin "44") (pinfunction "MTCK_44") (pintype "bidirectional"))
    )
    (net (code "57") (name "unconnected-(ESP32S3-MTDI-Pad47)") (class "Default")
      (node (ref "ESP32S3") (pin "47") (pinfunction "MTDI_47") (pintype "bidirectional"))
    )
    (net (code "58") (name "unconnected-(ESP32S3-MTDO-Pad45)") (class "Default")
      (node (ref "ESP32S3") (pin "45") (pinfunction "MTDO_45") (pintype "bidirectional"))
    )
    (net (code "59") (name "unconnected-(ESP32S3-MTMS-Pad48)") (class "Default")
      (node (ref "ESP32S3") (pin "48") (pinfunction "MTMS_48") (pintype "bidirectional"))
    )
    (net (code "60") (name "unconnected-(ESP32S3-SPICLK_N-Pad36)") (class "Default")
      (node (ref "ESP32S3") (pin "36") (pinfunction "SPICLK_N_36") (pintype "bidirectional"))
    )
    (net (code "61") (name "unconnected-(ESP32S3-SPICLK_P-Pad37)") (class "Default")
      (node (ref "ESP32S3") (pin "37") (pinfunction "SPICLK_P_37") (pintype "bidirectional"))
    )
    (net (code "62") (name "unconnected-(ESP32S3-XTAL_32K_N-Pad22)") (class "Default")
      (node (ref "ESP32S3") (pin "22") (pinfunction "XTAL_32K_N_22") (pintype "bidirectional"))
    )
    (net (code "63") (name "unconnected-(ESP32S3-XTAL_32K_P-Pad21)") (class "Default")
      (node (ref "ESP32S3") (pin "21") (pinfunction "XTAL_32K_P_21") (pintype "bidirectional"))
    )
    (net (code "64") (name "unconnected-(SW1-Pad1)") (class "Default")
      (node (ref "SW1") (pin "1") (pinfunction "1_1") (pintype "passive"))
    )
    (net (code "65") (name "unconnected-(SW1-Pad4)") (class "Default")
      (node (ref "SW1") (pin "4") (pinfunction "4_4") (pintype "passive"))
    )
    (net (code "66") (name "unconnected-(SW2-Pad2)") (class "Default")
      (node (ref "SW2") (pin "2") (pinfunction "2_2") (pintype "passive"))
    )
    (net (code "67") (name "unconnected-(SW2-Pad3)") (class "Default")
      (node (ref "SW2") (pin "3") (pinfunction "3_3") (pintype "passive"))
    )
    (net (code "68") (name "unconnected-(UART_BRIDGEA-SUSPEND-Pad12)") (class "Default")
      (node (ref "UART_BRIDGE") (pin "12") (pinfunction "SUSPEND_12") (pintype "output"))
    )
    (net (code "69") (name "unconnected-(UART_BRIDGEA-~{CTS}-Pad23)") (class "Default")
      (node (ref "UART_BRIDGE") (pin "23") (pinfunction "~{CTS}_23") (pintype "input+no_connect"))
    )
    (net (code "70") (name "unconnected-(UART_BRIDGEA-~{DCD}-Pad1)") (class "Default")
      (node (ref "UART_BRIDGE") (pin "1") (pinfunction "~{DCD}_1") (pintype "input+no_connect"))
    )
    (net (code "71") (name "unconnected-(UART_BRIDGEA-~{DSR}-Pad27)") (class "Default")
      (node (ref "UART_BRIDGE") (pin "27") (pinfunction "~{DSR}_27") (pintype "input+no_connect"))
    )
    (net (code "72") (name "unconnected-(UART_BRIDGEA-~{DTR}-Pad28)") (class "Default")
      (node (ref "UART_BRIDGE") (pin "28") (pinfunction "~{DTR}_28") (pintype "output"))
    )
    (net (code "73") (name "unconnected-(UART_BRIDGEA-~{RI}-Pad2)") (class "Default")
      (node (ref "UART_BRIDGE") (pin "2") (pinfunction "~{RI}_2") (pintype "input+no_connect"))
    )
    (net (code "74") (name "unconnected-(UART_BRIDGEA-~{RST}-Pad9)") (class "Default")
      (node (ref "UART_BRIDGE") (pin "9") (pinfunction "~{RST}_9") (pintype "bidirectional"))
    )
    (net (code "75") (name "unconnected-(UART_BRIDGEA-~{RTS}-Pad24)") (class "Default")
      (node (ref "UART_BRIDGE") (pin "24") (pinfunction "~{RTS}_24") (pintype "output"))
    )
    (net (code "76") (name "unconnected-(UART_BRIDGEA-~{SUSPEND}-Pad11)") (class "Default")
      (node (ref "UART_BRIDGE") (pin "11") (pinfunction "~{SUSPEND}_11") (pintype "output"))
    )
    (net (code "77") (name "unconnected-(UART_BRIDGEB-NC-Pad10)") (class "Default")
      (node (ref "UART_BRIDGE") (pin "10") (pinfunction "NC_10") (pintype "passive+no_connect"))
    )
    (net (code "78") (name "unconnected-(UART_BRIDGEB-NC-Pad13)") (class "Default")
      (node (ref "UART_BRIDGE") (pin "13") (pinfunction "NC_13") (pintype "passive+no_connect"))
    )
    (net (code "79") (name "unconnected-(UART_BRIDGEB-NC-Pad14)") (class "Default")
      (node (ref "UART_BRIDGE") (pin "14") (pinfunction "NC_14") (pintype "passive+no_connect"))
    )
    (net (code "80") (name "unconnected-(UART_BRIDGEB-NC-Pad15)") (class "Default")
      (node (ref "UART_BRIDGE") (pin "15") (pinfunction "NC_15") (pintype "passive+no_connect"))
    )
    (net (code "81") (name "unconnected-(UART_BRIDGEB-NC-Pad16)") (class "Default")
      (node (ref "UART_BRIDGE") (pin "16") (pinfunction "NC_16") (pintype "passive+no_connect"))
    )
    (net (code "82") (name "unconnected-(UART_BRIDGEB-NC-Pad17)") (class "Default")
      (node (ref "UART_BRIDGE") (pin "17") (pinfunction "NC_17") (pintype "passive+no_connect"))
    )
    (net (code "83") (name "unconnected-(UART_BRIDGEB-NC-Pad18)") (class "Default")
      (node (ref "UART_BRIDGE") (pin "18") (pinfunction "NC_18") (pintype "passive+no_connect"))
    )
    (net (code "84") (name "unconnected-(UART_BRIDGEB-NC-Pad19)") (class "Default")
      (node (ref "UART_BRIDGE") (pin "19") (pinfunction "NC_19") (pintype "passive+no_connect"))
    )
    (net (code "85") (name "unconnected-(UART_BRIDGEB-NC-Pad20)") (class "Default")
      (node (ref "UART_BRIDGE") (pin "20") (pinfunction "NC_20") (pintype "passive+no_connect"))
    )
    (net (code "86") (name "unconnected-(UART_BRIDGEB-NC-Pad21)") (class "Default")
      (node (ref "UART_BRIDGE") (pin "21") (pinfunction "NC_21") (pintype "passive+no_connect"))
    )
    (net (code "87") (name "unconnected-(UART_BRIDGEB-NC-Pad22)") (class "Default")
      (node (ref "UART_BRIDGE") (pin "22") (pinfunction "NC_22") (pintype "passive+no_connect"))
    )
    (net (code "88") (name "unconnected-(USB-C-2_D+-PadB6)") (class "Default")
      (node (ref "USB-C") (pin "B6") (pinfunction "2_D+_B6") (pintype "bidirectional+no_connect"))
    )
    (net (code "89") (name "unconnected-(USB-C-2_D--PadB7)") (class "Default")
      (node (ref "USB-C") (pin "B7") (pinfunction "2_D-_B7") (pintype "bidirectional+no_connect"))
    )
    (net (code "90") (name "unconnected-(USB-C-RX1+-PadB11)") (class "Default")
      (node (ref "USB-C") (pin "B11") (pinfunction "RX1+_B11") (pintype "input+no_connect"))
    )
    (net (code "91") (name "unconnected-(USB-C-RX1--PadB10)") (class "Default")
      (node (ref "USB-C") (pin "B10") (pinfunction "RX1-_B10") (pintype "input+no_connect"))
    )
    (net (code "92") (name "unconnected-(USB-C-RX2+-PadA11)") (class "Default")
      (node (ref "USB-C") (pin "A11") (pinfunction "RX2+_A11") (pintype "input+no_connect"))
    )
    (net (code "93") (name "unconnected-(USB-C-RX2--PadA10)") (class "Default")
      (node (ref "USB-C") (pin "A10") (pinfunction "RX2-_A10") (pintype "input+no_connect"))
    )
    (net (code "94") (name "unconnected-(USB-C-SBU1-PadA8)") (class "Default")
      (node (ref "USB-C") (pin "A8") (pinfunction "SBU1_A8") (pintype "passive+no_connect"))
    )
    (net (code "95") (name "unconnected-(USB-C-SBU2-PadB8)") (class "Default")
      (node (ref "USB-C") (pin "B8") (pinfunction "SBU2_B8") (pintype "passive+no_connect"))
    )
    (net (code "96") (name "unconnected-(USB-C-SHELL-Pad1)") (class "Default")
      (node (ref "USB-C") (pin "1") (pinfunction "SHELL_1") (pintype "passive+no_connect"))
    )
    (net (code "97") (name "unconnected-(USB-C-SHELL-Pad2)") (class "Default")
      (node (ref "USB-C") (pin "2") (pinfunction "SHELL_2") (pintype "passive+no_connect"))
    )
    (net (code "98") (name "unconnected-(USB-C-SHELL-Pad3)") (class "Default")
      (node (ref "USB-C") (pin "3") (pinfunction "SHELL_3") (pintype "passive+no_connect"))
    )
    (net (code "99") (name "unconnected-(USB-C-SHELL-Pad4)") (class "Default")
      (node (ref "USB-C") (pin "4") (pinfunction "SHELL_4") (pintype "passive+no_connect"))
    )
    (net (code "100") (name "unconnected-(USB-C-TX1+-PadA2)") (class "Default")
      (node (ref "USB-C") (pin "A2") (pinfunction "TX1+_A2") (pintype "output+no_connect"))
    )
    (net (code "101") (name "unconnected-(USB-C-TX1--PadA3)") (class "Default")
      (node (ref "USB-C") (pin "A3") (pinfunction "TX1-_A3") (pintype "output+no_connect"))
    )
    (net (code "102") (name "unconnected-(USB-C-TX2+-PadB2)") (class "Default")
      (node (ref "USB-C") (pin "B2") (pinfunction "TX2+_B2") (pintype "output+no_connect"))
    )
    (net (code "103") (name "unconnected-(USB-C-TX2--PadB3)") (class "Default")
      (node (ref "USB-C") (pin "B3") (pinfunction "TX2-_B3") (pintype "output+no_connect"))
    )
  )
)
